# microphone.net
KiCad netlist of a schematic drawn in EAGLE
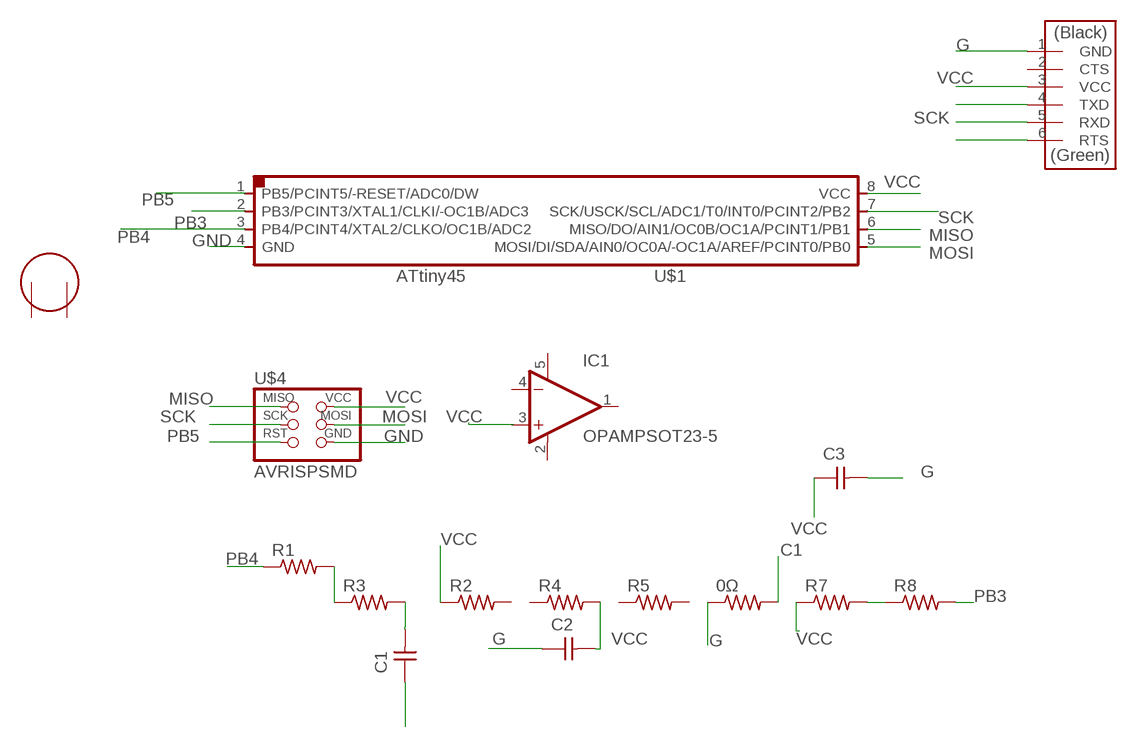
[diagram p0: schematic, sheet 1]

(export (version "E")
  (design (tool "Eeschema 10.0.6"))
  (components
    (comp (ref "0Ω")
      (value "RES-US1206FAB")
      (footprint "eagle-import:R1206FAB")
      (libsource (lib "eagle-import") (part "RES-US1206FAB"))
    )
    (comp (ref "C1")
      (value "CAP-UNPOLARIZEDFAB")
      (footprint "eagle-import:C1206FAB")
      (libsource (lib "eagle-import") (part "CAP-UNPOLARIZEDFAB"))
    )
    (comp (ref "C2")
      (value "CAP-UNPOLARIZEDFAB")
      (footprint "eagle-import:C1206FAB")
      (libsource (lib "eagle-import") (part "CAP-UNPOLARIZEDFAB"))
    )
    (comp (ref "C3")
      (value "CAP-UNPOLARIZEDFAB")
      (footprint "eagle-import:C1206FAB")
      (libsource (lib "eagle-import") (part "CAP-UNPOLARIZEDFAB"))
    )
    (comp (ref "IC1")
      (value "OPAMPSOT23-5")
      (footprint "eagle-import:SOT23-5")
      (libsource (lib "eagle-import") (part "OPAMPSOT23-5"))
    )
    (comp (ref "R1")
      (value "RES-US1206FAB")
      (footprint "eagle-import:R1206FAB")
      (libsource (lib "eagle-import") (part "RES-US1206FAB"))
    )
    (comp (ref "R2")
      (value "RES-US1206FAB")
      (footprint "eagle-import:R1206FAB")
      (libsource (lib "eagle-import") (part "RES-US1206FAB"))
    )
    (comp (ref "R3")
      (value "RES-US1206FAB")
      (footprint "eagle-import:R1206FAB")
      (libsource (lib "eagle-import") (part "RES-US1206FAB"))
    )
    (comp (ref "R4")
      (value "RES-US1206FAB")
      (footprint "eagle-import:R1206FAB")
      (libsource (lib "eagle-import") (part "RES-US1206FAB"))
    )
    (comp (ref "R5")
      (value "RES-US1206FAB")
      (footprint "eagle-import:R1206FAB")
      (libsource (lib "eagle-import") (part "RES-US1206FAB"))
    )
    (comp (ref "R7")
      (value "RES-US1206FAB")
      (footprint "eagle-import:R1206FAB")
      (libsource (lib "eagle-import") (part "RES-US1206FAB"))
    )
    (comp (ref "R8")
      (value "RES-US1206FAB")
      (footprint "eagle-import:R1206FAB")
      (libsource (lib "eagle-import") (part "RES-US1206FAB"))
    )
    (comp (ref "U$1")
      (value "ATTINY45SI")
      (footprint "eagle-import:SOIC8")
      (libsource (lib "eagle-import") (part "ATTINY45SI"))
    )
    (comp (ref "U$2")
      (value "FTDI-SMD-HEADER")
      (footprint "eagle-import:1X06SMD")
      (libsource (lib "eagle-import") (part "FTDI-SMD-HEADER"))
    )
    (comp (ref "U$4")
      (value "AVRISPSMD")
      (footprint "eagle-import:2X03SMD")
      (libsource (lib "eagle-import") (part "AVRISPSMD"))
    )
    (comp (ref "U$5")
      (value "ELECTRET")
      (footprint "eagle-import:ELECTRET_2742PBJ-A")
      (libsource (lib "eagle-import") (part "ELECTRET"))
    )
  )
  (nets
    (net (code "1") (name "/C1") (class "Default")
      (node (ref "0Ω") (pin "2") (pinfunction "2_2") (pintype "passive"))
    )
    (net (code "2") (name "/G") (class "Default")
      (node (ref "0Ω") (pin "1") (pinfunction "1_1") (pintype "passive"))
      (node (ref "C2") (pin "1") (pinfunction "1_1") (pintype "passive"))
      (node (ref "C3") (pin "2") (pinfunction "2_2") (pintype "passive"))
      (node (ref "U$2") (pin "1") (pinfunction "GND_1") (pintype "bidirectional"))
    )
    (net (code "3") (name "/GND") (class "Default")
      (node (ref "U$1") (pin "4") (pinfunction "GND_4") (pintype "bidirectional"))
      (node (ref "U$4") (pin "6") (pinfunction "GND_6") (pintype "passive"))
    )
    (net (code "4") (name "/MISO") (class "Default")
      (node (ref "U$1") (pin "6") (pinfunction "MISO/DO/AIN1/OC0B/OC1A/PCINT1/PB1_6") (pintype "bidirectional"))
      (node (ref "U$4") (pin "1") (pinfunction "MISO_1") (pintype "passive"))
    )
    (net (code "5") (name "/MOSI") (class "Default")
      (node (ref "U$1") (pin "5") (pinfunction "MOSI/DI/SDA/AIN0/OC0A/-OC1A/AREF/PCINT0/PB0_5") (pintype "bidirectional"))
      (node (ref "U$4") (pin "4") (pinfunction "MOSI_4") (pintype "passive"))
    )
    (net (code "6") (name "/PB3") (class "Default")
      (node (ref "R8") (pin "2") (pinfunction "2_2") (pintype "passive"))
      (node (ref "U$1") (pin "2") (pinfunction "PB3/PCINT3/XTAL1/CLKI/-OC1B/ADC3_2") (pintype "bidirectional"))
    )
    (net (code "7") (name "/PB4") (class "Default")
      (node (ref "R1") (pin "1") (pinfunction "1_1") (pintype "passive"))
      (node (ref "U$1") (pin "3") (pinfunction "PB4/PCINT4/XTAL2/CLKO/OC1B/ADC2_3") (pintype "bidirectional"))
    )
    (net (code "8") (name "/PB5") (class "Default")
      (node (ref "U$1") (pin "1") (pinfunction "PB5/PCINT5/-RESET/ADC0/DW_1") (pintype "bidirectional"))
      (node (ref "U$4") (pin "5") (pinfunction "RST_5") (pintype "passive"))
    )
    (net (code "9") (name "/SCK") (class "Default")
      (node (ref "U$1") (pin "7") (pinfunction "SCK/USCK/SCL/ADC1/T0/INT0/PCINT2/PB2_7") (pintype "bidirectional"))
      (node (ref "U$2") (pin "5") (pinfunction "RXD_5") (pintype "bidirectional"))
      (node (ref "U$4") (pin "3") (pinfunction "SCK_3") (pintype "passive"))
    )
    (net (code "10") (name "/V+") (class "Default")
      (node (ref "IC1") (pin "5") (pinfunction "V+_5") (pintype "power_in"))
    )
    (net (code "11") (name "/V-") (class "Default")
      (node (ref "IC1") (pin "2") (pinfunction "V-_2") (pintype "power_in"))
    )
    (net (code "12") (name "/VCC") (class "Default")
      (node (ref "C2") (pin "2") (pinfunction "2_2") (pintype "passive"))
      (node (ref "C3") (pin "1") (pinfunction "1_1") (pintype "passive"))
      (node (ref "R2") (pin "1") (pinfunction "1_1") (pintype "passive"))
      (node (ref "R4") (pin "2") (pinfunction "2_2") (pintype "passive"))
      (node (ref "R7") (pin "1") (pinfunction "1_1") (pintype "passive"))
      (node (ref "U$1") (pin "8") (pinfunction "VCC_8") (pintype "bidirectional"))
      (node (ref "U$2") (pin "3") (pinfunction "VCC_3") (pintype "bidirectional"))
      (node (ref "U$4") (pin "2") (pinfunction "VCC_2") (pintype "passive"))
    )
    (net (code "13") (name "Net-(C1-Pad2)") (class "Default")
      (node (ref "C1") (pin "2") (pinfunction "2_2") (pintype "passive"))
      (node (ref "R3") (pin "2") (pinfunction "2_2") (pintype "passive"))
    )
    (net (code "14") (name "Net-(R1-Pad2)") (class "Default")
      (node (ref "R1") (pin "2") (pinfunction "2_2") (pintype "passive"))
      (node (ref "R3") (pin "1") (pinfunction "1_1") (pintype "passive"))
    )
    (net (code "15") (name "Net-(R7-Pad2)") (class "Default")
      (node (ref "R7") (pin "2") (pinfunction "2_2") (pintype "passive"))
      (node (ref "R8") (pin "1") (pinfunction "1_1") (pintype "passive"))
    )
    (net (code "16") (name "unconnected-(C1-Pad1)") (class "Default")
      (node (ref "C1") (pin "1") (pinfunction "1_1") (pintype "passive"))
    )
    (net (code "17") (name "unconnected-(IC1-+IN-Pad3)") (class "Default")
      (node (ref "IC1") (pin "3") (pinfunction "+IN_3") (pintype "input"))
    )
    (net (code "18") (name "unconnected-(IC1--IN-Pad4)") (class "Default")
      (node (ref "IC1") (pin "4") (pinfunction "-IN_4") (pintype "input"))
    )
    (net (code "19") (name "unconnected-(IC1-OUT-Pad1)") (class "Default")
      (node (ref "IC1") (pin "1") (pinfunction "OUT_1") (pintype "output"))
    )
    (net (code "20") (name "unconnected-(R2-Pad2)") (class "Default")
      (node (ref "R2") (pin "2") (pinfunction "2_2") (pintype "passive"))
    )
    (net (code "21") (name "unconnected-(R4-Pad1)") (class "Default")
      (node (ref "R4") (pin "1") (pinfunction "1_1") (pintype "passive"))
    )
    (net (code "22") (name "unconnected-(R5-Pad1)") (class "Default")
      (node (ref "R5") (pin "1") (pinfunction "1_1") (pintype "passive"))
    )
    (net (code "23") (name "unconnected-(R5-Pad2)") (class "Default")
      (node (ref "R5") (pin "2") (pinfunction "2_2") (pintype "passive"))
    )
    (net (code "24") (name "unconnected-(U$2-CTS-Pad2)") (class "Default")
      (node (ref "U$2") (pin "2") (pinfunction "CTS_2") (pintype "bidirectional"))
    )
    (net (code "25") (name "unconnected-(U$2-RTS-Pad6)") (class "Default")
      (node (ref "U$2") (pin "6") (pinfunction "RTS_6") (pintype "bidirectional"))
    )
    (net (code "26") (name "unconnected-(U$2-TXD-Pad4)") (class "Default")
      (node (ref "U$2") (pin "4") (pinfunction "TXD_4") (pintype "bidirectional"))
    )
    (net (code "27") (name "unconnected-(U$5-PadP$1)") (class "Default")
      (node (ref "U$5") (pin "P$1") (pinfunction "P$1_P$1") (pintype "bidirectional"))
    )
    (net (code "28") (name "unconnected-(U$5-PadP$2)") (class "Default")
      (node (ref "U$5") (pin "P$2") (pinfunction "P$2_P$2") (pintype "bidirectional"))
    )
  )
)
